# rapport.net
KiCad netlist of a schematic drawn in EAGLE
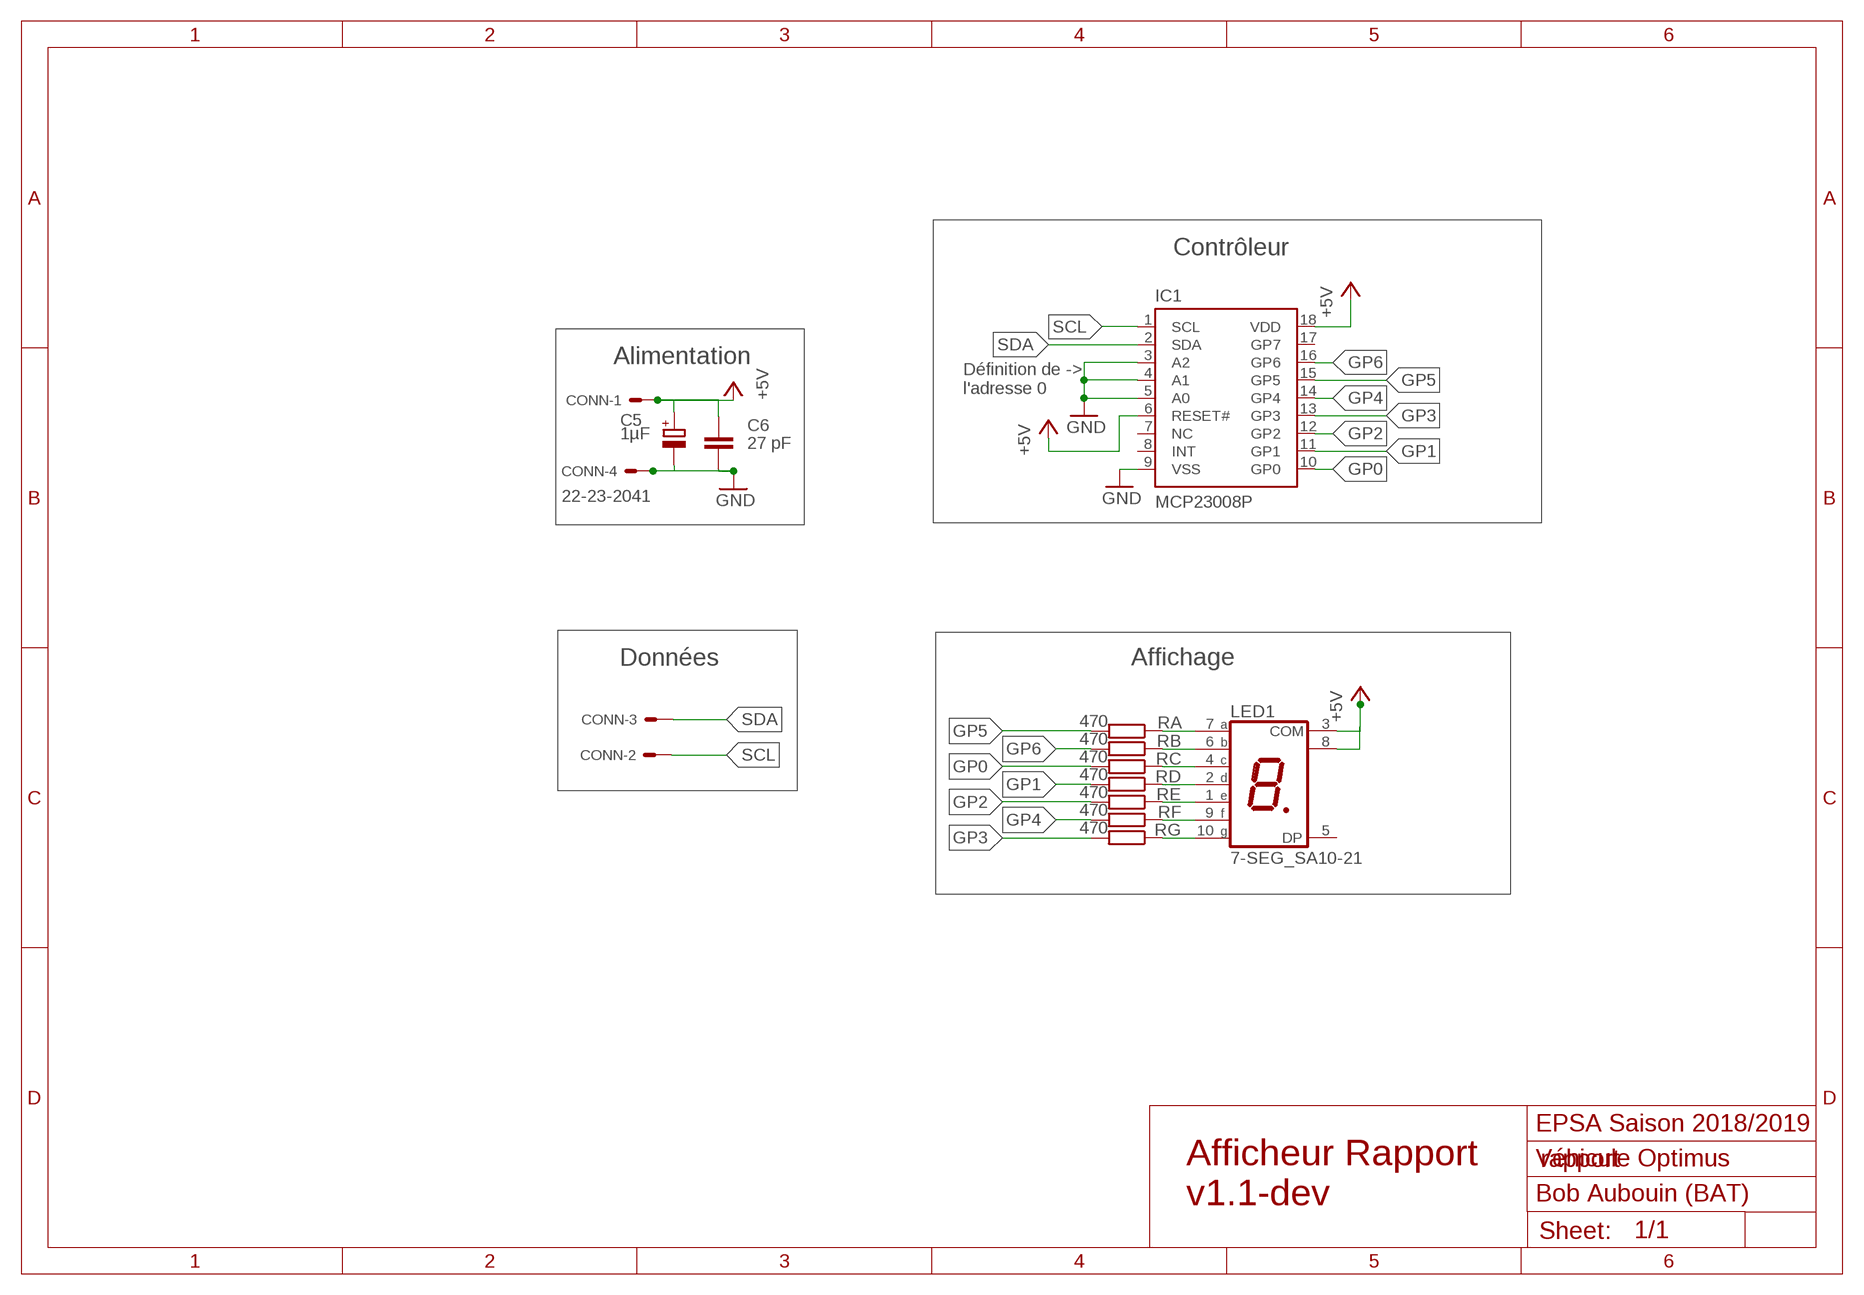
[diagram p0: schematic, sheet 1]

(export (version "E")
  (design (tool "Eeschema 10.0.6"))
  (components
    (comp (ref "C5")
      (value "1µF")
      (footprint "eagle-import:B45181A")
      (libsource (lib "eagle-import") (part "CPOL-EUB45181A"))
    )
    (comp (ref "C6")
      (value "27 pF")
      (footprint "eagle-import:C025-025X050")
      (libsource (lib "eagle-import") (part "C-EU025-025X050"))
    )
    (comp (ref "CONN")
      (value "22-23-2041")
      (footprint "eagle-import:22-23-2041")
      (fields (field (name "MF") "MOLEX"))
      (libsource (lib "eagle-import") (part "22-23-2041"))
    )
    (comp (ref "IC1")
      (value "MCP23008P")
      (footprint "eagle-import:DIL18")
      (libsource (lib "eagle-import") (part "MCP23008P"))
    )
    (comp (ref "LED1")
      (value "7-SEG_SA10-21")
      (footprint "eagle-import:SA10-21")
      (libsource (lib "eagle-import") (part "7-SEG_SA10-21"))
    )
    (comp (ref "RA")
      (value "470")
      (footprint "eagle-import:0204_7")
      (libsource (lib "eagle-import") (part "R-EU_0204/7"))
    )
    (comp (ref "RB")
      (value "470")
      (footprint "eagle-import:0204_7")
      (libsource (lib "eagle-import") (part "R-EU_0204/7"))
    )
    (comp (ref "RC")
      (value "470")
      (footprint "eagle-import:0204_7")
      (libsource (lib "eagle-import") (part "R-EU_0204/7"))
    )
    (comp (ref "RD")
      (value "470")
      (footprint "eagle-import:0204_7")
      (libsource (lib "eagle-import") (part "R-EU_0204/7"))
    )
    (comp (ref "RE")
      (value "470")
      (footprint "eagle-import:0204_7")
      (libsource (lib "eagle-import") (part "R-EU_0204/7"))
    )
    (comp (ref "RF")
      (value "470")
      (footprint "eagle-import:0204_7")
      (libsource (lib "eagle-import") (part "R-EU_0204/7"))
    )
    (comp (ref "RG")
      (value "470")
      (footprint "eagle-import:0204_7")
      (libsource (lib "eagle-import") (part "R-EU_0204/7"))
    )
  )
  (nets
    (net (code "1") (name "+5V") (class "Default")
      (node (ref "C5") (pin "+") (pinfunction "+_+") (pintype "passive"))
      (node (ref "C6") (pin "1") (pinfunction "1_1") (pintype "passive"))
      (node (ref "CONN") (pin "1") (pinfunction "S_1") (pintype "passive"))
      (node (ref "IC1") (pin "18") (pinfunction "VDD_18") (pintype "power_in"))
      (node (ref "IC1") (pin "6") (pinfunction "RESET#_6") (pintype "input"))
      (node (ref "LED1") (pin "3") (pinfunction "COM_3") (pintype "passive"))
      (node (ref "LED1") (pin "8") (pinfunction "COM_8") (pintype "passive"))
    )
    (net (code "2") (name "GND") (class "Default")
      (node (ref "C5") (pin "-") (pinfunction "-_-") (pintype "passive"))
      (node (ref "C6") (pin "2") (pinfunction "2_2") (pintype "passive"))
      (node (ref "CONN") (pin "4") (pinfunction "S_4") (pintype "passive"))
      (node (ref "IC1") (pin "3") (pinfunction "A2_3") (pintype "input"))
      (node (ref "IC1") (pin "4") (pinfunction "A1_4") (pintype "input"))
      (node (ref "IC1") (pin "5") (pinfunction "A0_5") (pintype "input"))
      (node (ref "IC1") (pin "9") (pinfunction "VSS_9") (pintype "power_in"))
    )
    (net (code "3") (name "GP0") (class "Default")
      (node (ref "IC1") (pin "10") (pinfunction "GP0_10") (pintype "bidirectional"))
      (node (ref "RC") (pin "2") (pinfunction "2_2") (pintype "passive"))
    )
    (net (code "4") (name "GP1") (class "Default")
      (node (ref "IC1") (pin "11") (pinfunction "GP1_11") (pintype "bidirectional"))
      (node (ref "RD") (pin "2") (pinfunction "2_2") (pintype "passive"))
    )
    (net (code "5") (name "GP2") (class "Default")
      (node (ref "IC1") (pin "12") (pinfunction "GP2_12") (pintype "bidirectional"))
      (node (ref "RE") (pin "2") (pinfunction "2_2") (pintype "passive"))
    )
    (net (code "6") (name "GP3") (class "Default")
      (node (ref "IC1") (pin "13") (pinfunction "GP3_13") (pintype "bidirectional"))
      (node (ref "RG") (pin "2") (pinfunction "2_2") (pintype "passive"))
    )
    (net (code "7") (name "GP4") (class "Default")
      (node (ref "IC1") (pin "14") (pinfunction "GP4_14") (pintype "bidirectional"))
      (node (ref "RF") (pin "2") (pinfunction "2_2") (pintype "passive"))
    )
    (net (code "8") (name "GP5") (class "Default")
      (node (ref "IC1") (pin "15") (pinfunction "GP5_15") (pintype "bidirectional"))
      (node (ref "RA") (pin "2") (pinfunction "2_2") (pintype "passive"))
    )
    (net (code "9") (name "GP6") (class "Default")
      (node (ref "IC1") (pin "16") (pinfunction "GP6_16") (pintype "bidirectional"))
      (node (ref "RB") (pin "2") (pinfunction "2_2") (pintype "passive"))
    )
    (net (code "10") (name "Net-(LED1-A)") (class "Default")
      (node (ref "LED1") (pin "7") (pinfunction "A_7") (pintype "passive"))
      (node (ref "RA") (pin "1") (pinfunction "1_1") (pintype "passive"))
    )
    (net (code "11") (name "Net-(LED1-B)") (class "Default")
      (node (ref "LED1") (pin "6") (pinfunction "B_6") (pintype "passive"))
      (node (ref "RB") (pin "1") (pinfunction "1_1") (pintype "passive"))
    )
    (net (code "12") (name "Net-(LED1-C)") (class "Default")
      (node (ref "LED1") (pin "4") (pinfunction "C_4") (pintype "passive"))
      (node (ref "RC") (pin "1") (pinfunction "1_1") (pintype "passive"))
    )
    (net (code "13") (name "Net-(LED1-D)") (class "Default")
      (node (ref "LED1") (pin "2") (pinfunction "D_2") (pintype "passive"))
      (node (ref "RD") (pin "1") (pinfunction "1_1") (pintype "passive"))
    )
    (net (code "14") (name "Net-(LED1-E)") (class "Default")
      (node (ref "LED1") (pin "1") (pinfunction "E_1") (pintype "passive"))
      (node (ref "RE") (pin "1") (pinfunction "1_1") (pintype "passive"))
    )
    (net (code "15") (name "Net-(LED1-F)") (class "Default")
      (node (ref "LED1") (pin "9") (pinfunction "F_9") (pintype "passive"))
      (node (ref "RF") (pin "1") (pinfunction "1_1") (pintype "passive"))
    )
    (net (code "16") (name "Net-(LED1-G)") (class "Default")
      (node (ref "LED1") (pin "10") (pinfunction "G_10") (pintype "passive"))
      (node (ref "RG") (pin "1") (pinfunction "1_1") (pintype "passive"))
    )
    (net (code "17") (name "SCL") (class "Default")
      (node (ref "CONN") (pin "2") (pinfunction "S_2") (pintype "passive"))
      (node (ref "IC1") (pin "1") (pinfunction "SCL_1") (pintype "input"))
    )
    (net (code "18") (name "SDA") (class "Default")
      (node (ref "CONN") (pin "3") (pinfunction "S_3") (pintype "passive"))
      (node (ref "IC1") (pin "2") (pinfunction "SDA_2") (pintype "bidirectional"))
    )
    (net (code "19") (name "unconnected-(IC1-GP7-Pad17)") (class "Default")
      (node (ref "IC1") (pin "17") (pinfunction "GP7_17") (pintype "bidirectional"))
    )
    (net (code "20") (name "unconnected-(IC1-INT-Pad8)") (class "Default")
      (node (ref "IC1") (pin "8") (pinfunction "INT_8") (pintype "output"))
    )
    (net (code "21") (name "unconnected-(IC1-NC-Pad7)") (class "Default")
      (node (ref "IC1") (pin "7") (pinfunction "NC_7") (pintype "no_connect"))
    )
    (net (code "22") (name "unconnected-(LED1-DP-Pad5)") (class "Default")
      (node (ref "LED1") (pin "5") (pinfunction "DP_5") (pintype "passive"))
    )
  )
)
